# Krobot_UI.net
KiCad netlist of a schematic drawn in EAGLE
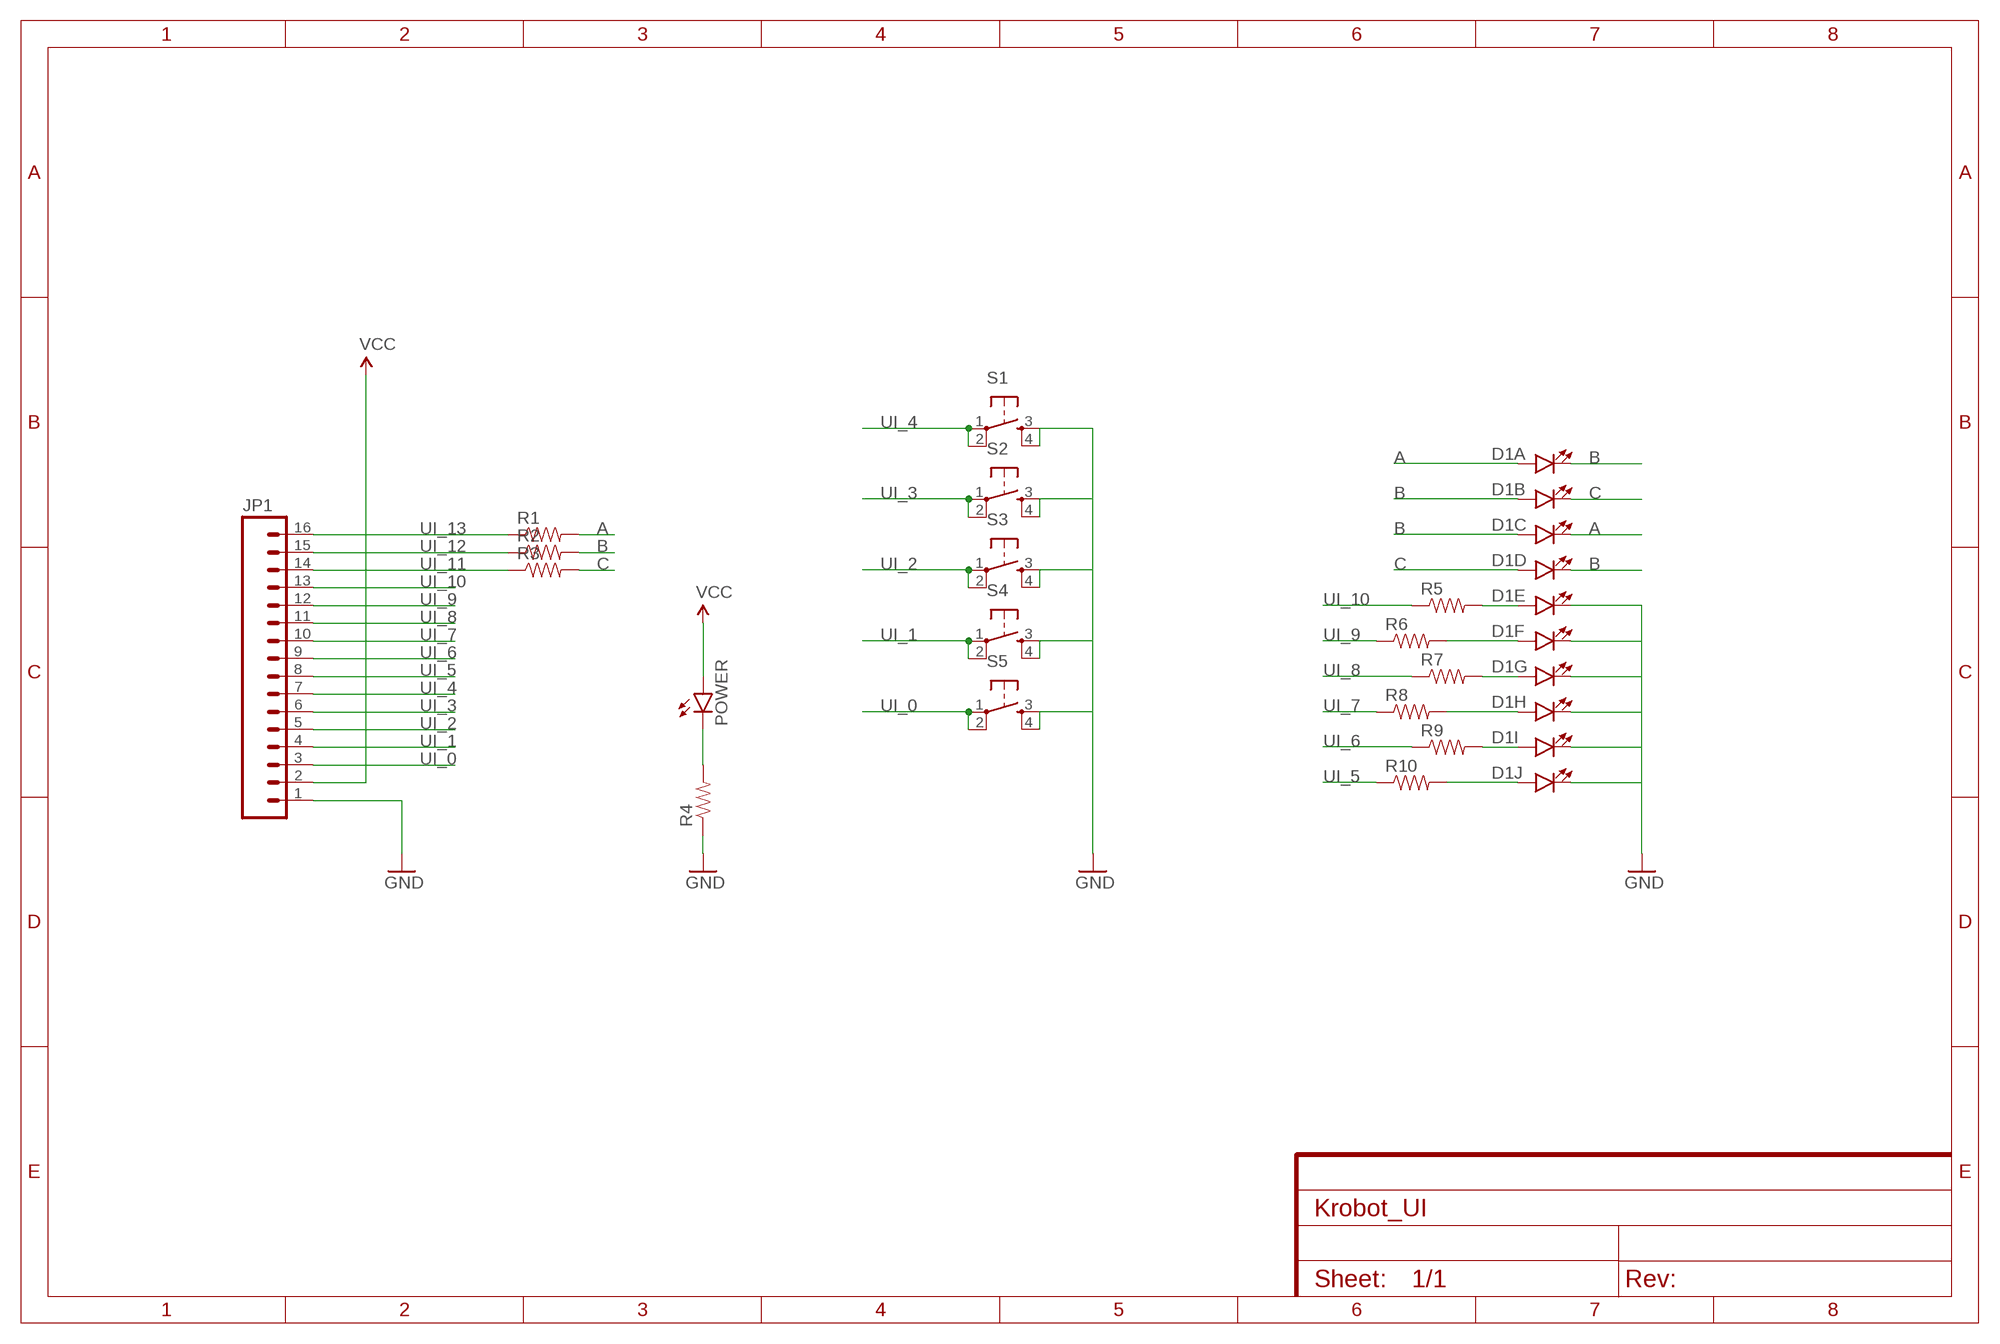
[diagram p0: schematic, sheet 1]

(export (version "E")
  (design (tool "Eeschema 10.0.6"))
  (components
    (comp (ref "D1")
      (value "LED_BARGRAPH_10")
      (footprint "eagle-import:LED_BARGAPH_10")
      (libsource (lib "eagle-import") (part "LED_BARGRAPH_10"))
    )
    (comp (ref "JP1")
      (value "M16LONGPADS")
      (footprint "eagle-import:1X16_LONGPADS")
      (libsource (lib "eagle-import") (part "M16LONGPADS"))
    )
    (comp (ref "POWER")
      (value "LED1206")
      (footprint "eagle-import:LED-1206")
      (libsource (lib "eagle-import") (part "LED1206"))
    )
    (comp (ref "R1")
      (value "RESISTOR1206")
      (footprint "eagle-import:1206")
      (libsource (lib "eagle-import") (part "RESISTOR1206"))
    )
    (comp (ref "R2")
      (value "RESISTOR1206")
      (footprint "eagle-import:1206")
      (libsource (lib "eagle-import") (part "RESISTOR1206"))
    )
    (comp (ref "R3")
      (value "RESISTOR1206")
      (footprint "eagle-import:1206")
      (libsource (lib "eagle-import") (part "RESISTOR1206"))
    )
    (comp (ref "R4")
      (value "RESISTOR1206")
      (footprint "eagle-import:1206")
      (libsource (lib "eagle-import") (part "RESISTOR1206"))
    )
    (comp (ref "R5")
      (value "RESISTOR1206")
      (footprint "eagle-import:1206")
      (libsource (lib "eagle-import") (part "RESISTOR1206"))
    )
    (comp (ref "R6")
      (value "RESISTOR1206")
      (footprint "eagle-import:1206")
      (libsource (lib "eagle-import") (part "RESISTOR1206"))
    )
    (comp (ref "R7")
      (value "RESISTOR1206")
      (footprint "eagle-import:1206")
      (libsource (lib "eagle-import") (part "RESISTOR1206"))
    )
    (comp (ref "R8")
      (value "RESISTOR1206")
      (footprint "eagle-import:1206")
      (libsource (lib "eagle-import") (part "RESISTOR1206"))
    )
    (comp (ref "R9")
      (value "RESISTOR1206")
      (footprint "eagle-import:1206")
      (libsource (lib "eagle-import") (part "RESISTOR1206"))
    )
    (comp (ref "R10")
      (value "RESISTOR1206")
      (footprint "eagle-import:1206")
      (libsource (lib "eagle-import") (part "RESISTOR1206"))
    )
    (comp (ref "S1")
      (value "TAC_SWITCHPTH")
      (footprint "eagle-import:TACTILE-PTH")
      (libsource (lib "eagle-import") (part "TAC_SWITCHPTH"))
    )
    (comp (ref "S2")
      (value "TAC_SWITCHPTH")
      (footprint "eagle-import:TACTILE-PTH")
      (libsource (lib "eagle-import") (part "TAC_SWITCHPTH"))
    )
    (comp (ref "S3")
      (value "TAC_SWITCHPTH")
      (footprint "eagle-import:TACTILE-PTH")
      (libsource (lib "eagle-import") (part "TAC_SWITCHPTH"))
    )
    (comp (ref "S4")
      (value "TAC_SWITCHPTH")
      (footprint "eagle-import:TACTILE-PTH")
      (libsource (lib "eagle-import") (part "TAC_SWITCHPTH"))
    )
    (comp (ref "S5")
      (value "TAC_SWITCHPTH")
      (footprint "eagle-import:TACTILE-PTH")
      (libsource (lib "eagle-import") (part "TAC_SWITCHPTH"))
    )
  )
  (nets
    (net (code "1") (name "/A") (class "Default")
      (node (ref "D1") (pin "1") (pinfunction "A_1") (pintype "passive"))
      (node (ref "D1") (pin "18") (pinfunction "C_18") (pintype "passive"))
      (node (ref "R1") (pin "2") (pinfunction "2_2") (pintype "passive"))
    )
    (net (code "2") (name "/B") (class "Default")
      (node (ref "D1") (pin "17") (pinfunction "C_17") (pintype "passive"))
      (node (ref "D1") (pin "2") (pinfunction "A_2") (pintype "passive"))
      (node (ref "D1") (pin "20") (pinfunction "C_20") (pintype "passive"))
      (node (ref "D1") (pin "3") (pinfunction "A_3") (pintype "passive"))
      (node (ref "R2") (pin "2") (pinfunction "2_2") (pintype "passive"))
    )
    (net (code "3") (name "/C") (class "Default")
      (node (ref "D1") (pin "19") (pinfunction "C_19") (pintype "passive"))
      (node (ref "D1") (pin "4") (pinfunction "A_4") (pintype "passive"))
      (node (ref "R3") (pin "2") (pinfunction "2_2") (pintype "passive"))
    )
    (net (code "4") (name "/UI_0") (class "Default")
      (node (ref "JP1") (pin "3") (pinfunction "3_3") (pintype "passive"))
      (node (ref "S5") (pin "1") (pinfunction "1_1") (pintype "passive"))
      (node (ref "S5") (pin "2") (pinfunction "2_2") (pintype "passive"))
    )
    (net (code "5") (name "/UI_1") (class "Default")
      (node (ref "JP1") (pin "4") (pinfunction "4_4") (pintype "passive"))
      (node (ref "S4") (pin "1") (pinfunction "1_1") (pintype "passive"))
      (node (ref "S4") (pin "2") (pinfunction "2_2") (pintype "passive"))
    )
    (net (code "6") (name "/UI_2") (class "Default")
      (node (ref "JP1") (pin "5") (pinfunction "5_5") (pintype "passive"))
      (node (ref "S3") (pin "1") (pinfunction "1_1") (pintype "passive"))
      (node (ref "S3") (pin "2") (pinfunction "2_2") (pintype "passive"))
    )
    (net (code "7") (name "/UI_3") (class "Default")
      (node (ref "JP1") (pin "6") (pinfunction "6_6") (pintype "passive"))
      (node (ref "S2") (pin "1") (pinfunction "1_1") (pintype "passive"))
      (node (ref "S2") (pin "2") (pinfunction "2_2") (pintype "passive"))
    )
    (net (code "8") (name "/UI_4") (class "Default")
      (node (ref "JP1") (pin "7") (pinfunction "7_7") (pintype "passive"))
      (node (ref "S1") (pin "1") (pinfunction "1_1") (pintype "passive"))
      (node (ref "S1") (pin "2") (pinfunction "2_2") (pintype "passive"))
    )
    (net (code "9") (name "/UI_5") (class "Default")
      (node (ref "JP1") (pin "8") (pinfunction "8_8") (pintype "passive"))
      (node (ref "R10") (pin "1") (pinfunction "1_1") (pintype "passive"))
    )
    (net (code "10") (name "/UI_6") (class "Default")
      (node (ref "JP1") (pin "9") (pinfunction "9_9") (pintype "passive"))
      (node (ref "R9") (pin "1") (pinfunction "1_1") (pintype "passive"))
    )
    (net (code "11") (name "/UI_7") (class "Default")
      (node (ref "JP1") (pin "10") (pinfunction "10_10") (pintype "passive"))
      (node (ref "R8") (pin "1") (pinfunction "1_1") (pintype "passive"))
    )
    (net (code "12") (name "/UI_8") (class "Default")
      (node (ref "JP1") (pin "11") (pinfunction "11_11") (pintype "passive"))
      (node (ref "R7") (pin "1") (pinfunction "1_1") (pintype "passive"))
    )
    (net (code "13") (name "/UI_9") (class "Default")
      (node (ref "JP1") (pin "12") (pinfunction "12_12") (pintype "passive"))
      (node (ref "R6") (pin "1") (pinfunction "1_1") (pintype "passive"))
    )
    (net (code "14") (name "/UI_10") (class "Default")
      (node (ref "JP1") (pin "13") (pinfunction "13_13") (pintype "passive"))
      (node (ref "R5") (pin "1") (pinfunction "1_1") (pintype "passive"))
    )
    (net (code "15") (name "/UI_11") (class "Default")
      (node (ref "JP1") (pin "14") (pinfunction "14_14") (pintype "passive"))
      (node (ref "R3") (pin "1") (pinfunction "1_1") (pintype "passive"))
    )
    (net (code "16") (name "/UI_12") (class "Default")
      (node (ref "JP1") (pin "15") (pinfunction "15_15") (pintype "passive"))
      (node (ref "R2") (pin "1") (pinfunction "1_1") (pintype "passive"))
    )
    (net (code "17") (name "/UI_13") (class "Default")
      (node (ref "JP1") (pin "16") (pinfunction "16_16") (pintype "passive"))
      (node (ref "R1") (pin "1") (pinfunction "1_1") (pintype "passive"))
    )
    (net (code "18") (name "GND") (class "Default")
      (node (ref "D1") (pin "11") (pinfunction "C_11") (pintype "passive"))
      (node (ref "D1") (pin "12") (pinfunction "C_12") (pintype "passive"))
      (node (ref "D1") (pin "13") (pinfunction "C_13") (pintype "passive"))
      (node (ref "D1") (pin "14") (pinfunction "C_14") (pintype "passive"))
      (node (ref "D1") (pin "15") (pinfunction "C_15") (pintype "passive"))
      (node (ref "D1") (pin "16") (pinfunction "C_16") (pintype "passive"))
      (node (ref "JP1") (pin "1") (pinfunction "1_1") (pintype "passive"))
      (node (ref "R4") (pin "1") (pinfunction "1_1") (pintype "passive"))
      (node (ref "S1") (pin "3") (pinfunction "3_3") (pintype "passive"))
      (node (ref "S1") (pin "4") (pinfunction "4_4") (pintype "passive"))
      (node (ref "S2") (pin "3") (pinfunction "3_3") (pintype "passive"))
      (node (ref "S2") (pin "4") (pinfunction "4_4") (pintype "passive"))
      (node (ref "S3") (pin "3") (pinfunction "3_3") (pintype "passive"))
      (node (ref "S3") (pin "4") (pinfunction "4_4") (pintype "passive"))
      (node (ref "S4") (pin "3") (pinfunction "3_3") (pintype "passive"))
      (node (ref "S4") (pin "4") (pinfunction "4_4") (pintype "passive"))
      (node (ref "S5") (pin "3") (pinfunction "3_3") (pintype "passive"))
      (node (ref "S5") (pin "4") (pinfunction "4_4") (pintype "passive"))
    )
    (net (code "19") (name "Net-(D1E-A)") (class "Default")
      (node (ref "D1") (pin "5") (pinfunction "A_5") (pintype "passive"))
      (node (ref "R5") (pin "2") (pinfunction "2_2") (pintype "passive"))
    )
    (net (code "20") (name "Net-(D1F-A)") (class "Default")
      (node (ref "D1") (pin "6") (pinfunction "A_6") (pintype "passive"))
      (node (ref "R6") (pin "2") (pinfunction "2_2") (pintype "passive"))
    )
    (net (code "21") (name "Net-(D1G-A)") (class "Default")
      (node (ref "D1") (pin "7") (pinfunction "A_7") (pintype "passive"))
      (node (ref "R7") (pin "2") (pinfunction "2_2") (pintype "passive"))
    )
    (net (code "22") (name "Net-(D1H-A)") (class "Default")
      (node (ref "D1") (pin "8") (pinfunction "A_8") (pintype "passive"))
      (node (ref "R8") (pin "2") (pinfunction "2_2") (pintype "passive"))
    )
    (net (code "23") (name "Net-(D1I-A)") (class "Default")
      (node (ref "D1") (pin "9") (pinfunction "A_9") (pintype "passive"))
      (node (ref "R9") (pin "2") (pinfunction "2_2") (pintype "passive"))
    )
    (net (code "24") (name "Net-(D1J-A)") (class "Default")
      (node (ref "D1") (pin "10") (pinfunction "A_10") (pintype "passive"))
      (node (ref "R10") (pin "2") (pinfunction "2_2") (pintype "passive"))
    )
    (net (code "25") (name "Net-(POWER-PadC)") (class "Default")
      (node (ref "POWER") (pin "C") (pinfunction "C_C") (pintype "passive"))
      (node (ref "R4") (pin "2") (pinfunction "2_2") (pintype "passive"))
    )
    (net (code "26") (name "VCC") (class "Default")
      (node (ref "JP1") (pin "2") (pinfunction "2_2") (pintype "passive"))
      (node (ref "POWER") (pin "A") (pinfunction "A_A") (pintype "passive"))
    )
  )
)
